# B5_EM__Y_SOLAR_PANEL.net
KiCad netlist of a schematic drawn in EAGLE
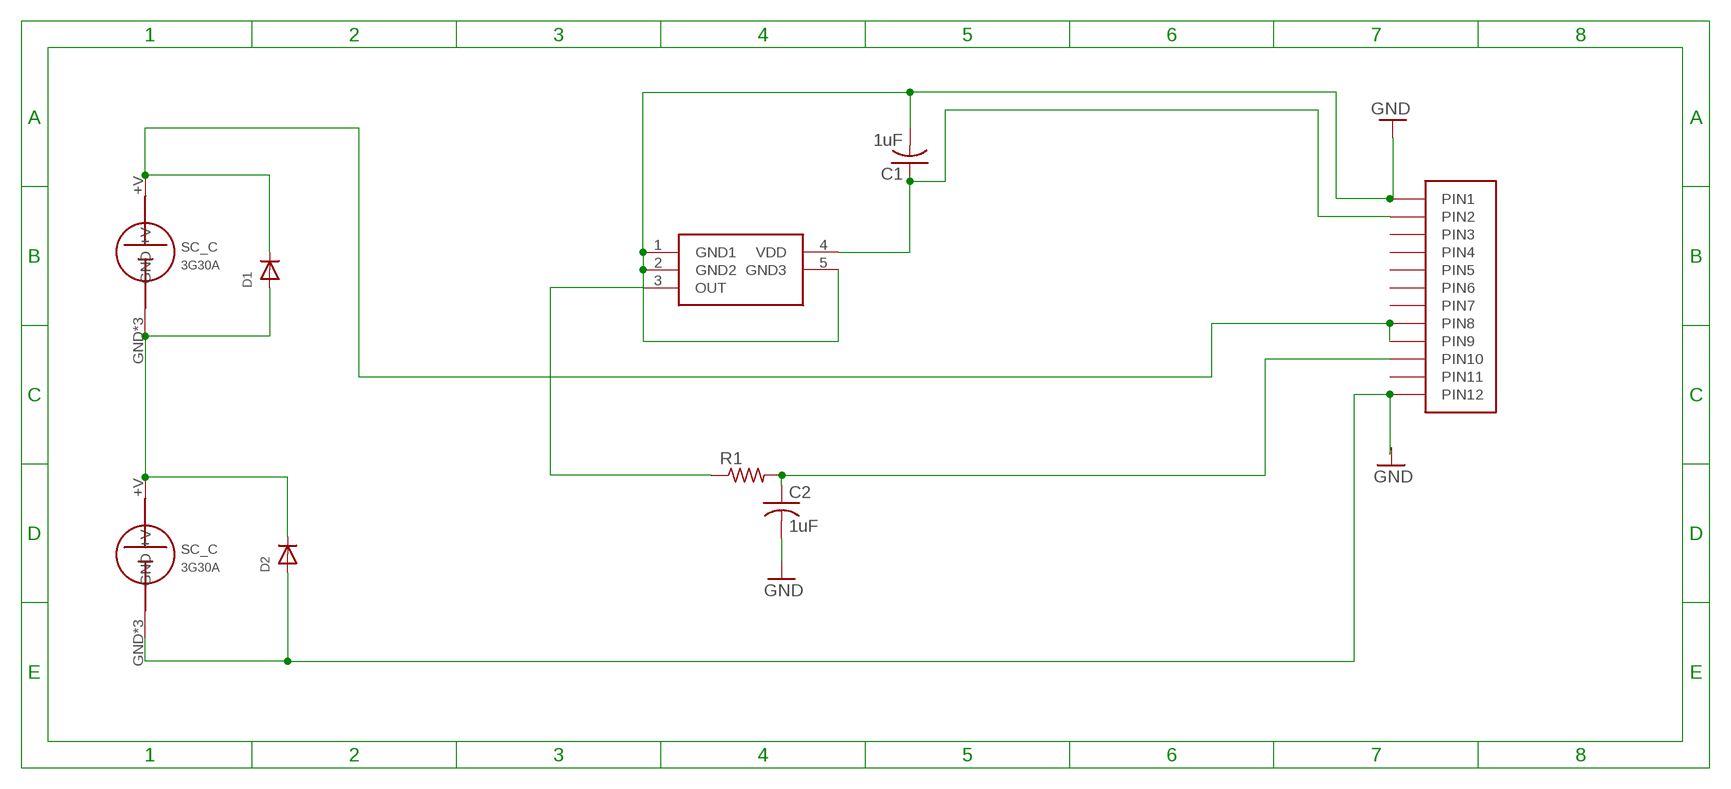
[diagram p0: schematic, sheet 1]

(export (version "E")
  (design (tool "Eeschema 10.0.6"))
  (components
    (comp (ref "C1")
      (value "1uF")
      (footprint "eagle-import:C0805")
      (libsource (lib "eagle-import") (part "C-USC0805"))
    )
    (comp (ref "C2")
      (value "1uF")
      (footprint "eagle-import:C0805")
      (libsource (lib "eagle-import") (part "C-USC0805"))
    )
    (comp (ref "D1")
      (value "DIODE_SOD-123FL")
      (footprint "eagle-import:SOD-123FL")
      (libsource (lib "eagle-import") (part "DIODE_SOD-123FL"))
    )
    (comp (ref "D2")
      (value "DIODE_SOD-123FL")
      (footprint "eagle-import:SOD-123FL")
      (libsource (lib "eagle-import") (part "DIODE_SOD-123FL"))
    )
    (comp (ref "R1")
      (value "R-US_R0402")
      (footprint "eagle-import:R0402")
      (libsource (lib "eagle-import") (part "R-US_R0402"))
    )
    (comp (ref "U$1")
      (value "HEADER12PIN")
      (footprint "eagle-import:HEADER12PIN")
      (libsource (lib "eagle-import") (part "HEADER12PIN"))
    )
    (comp (ref "U$3")
      (value "LMT84DCKT")
      (footprint "eagle-import:SOT65P210X110-5N")
      (fields (field (name "RS_PART_NUMBER") "8115860"))
      (libsource (lib "eagle-import") (part "LMT84DCKT"))
    )
    (comp (ref "U$4")
      (value "SC_C")
      (footprint "eagle-import:SC_C")
      (libsource (lib "eagle-import") (part "SC_C"))
    )
    (comp (ref "U$5")
      (value "SC_C")
      (footprint "eagle-import:SC_C")
      (libsource (lib "eagle-import") (part "SC_C"))
    )
  )
  (nets
    (net (code "1") (name "GND") (class "Default")
      (node (ref "C1") (pin "2") (pinfunction "2_2") (pintype "passive"))
      (node (ref "C2") (pin "2") (pinfunction "2_2") (pintype "passive"))
      (node (ref "D2") (pin "A") (pinfunction "A_A") (pintype "passive"))
      (node (ref "U$1") (pin "P1") (pinfunction "PIN1_P1") (pintype "bidirectional"))
      (node (ref "U$1") (pin "P12") (pinfunction "PIN12_P12") (pintype "bidirectional"))
      (node (ref "U$3") (pin "1") (pinfunction "GND1_1") (pintype "power_in"))
      (node (ref "U$3") (pin "2") (pinfunction "GND2_2") (pintype "power_in"))
      (node (ref "U$3") (pin "5") (pinfunction "GND3_5") (pintype "power_in"))
      (node (ref "U$4") (pin "GND") (pinfunction "GND_GND") (pintype "bidirectional"))
      (node (ref "U$4") (pin "GND1") (pinfunction "GND_GND1") (pintype "bidirectional"))
      (node (ref "U$4") (pin "GND2") (pinfunction "GND_GND2") (pintype "bidirectional"))
    )
    (net (code "2") (name "Net-(D1-PadA)") (class "Default")
      (node (ref "D1") (pin "A") (pinfunction "A_A") (pintype "passive"))
      (node (ref "D2") (pin "C") (pinfunction "C_C") (pintype "passive"))
      (node (ref "U$4") (pin "+V") (pinfunction "+V_+V") (pintype "bidirectional"))
      (node (ref "U$5") (pin "GND") (pinfunction "GND_GND") (pintype "bidirectional"))
      (node (ref "U$5") (pin "GND1") (pinfunction "GND_GND1") (pintype "bidirectional"))
      (node (ref "U$5") (pin "GND2") (pinfunction "GND_GND2") (pintype "bidirectional"))
    )
    (net (code "3") (name "Net-(U$1-PIN2)") (class "Default")
      (node (ref "C1") (pin "1") (pinfunction "1_1") (pintype "passive"))
      (node (ref "U$1") (pin "P2") (pinfunction "PIN2_P2") (pintype "bidirectional"))
      (node (ref "U$3") (pin "4") (pinfunction "VDD_4") (pintype "power_in"))
    )
    (net (code "4") (name "Net-(U$1-PIN8)") (class "Default")
      (node (ref "D1") (pin "C") (pinfunction "C_C") (pintype "passive"))
      (node (ref "U$1") (pin "P8") (pinfunction "PIN8_P8") (pintype "bidirectional"))
      (node (ref "U$1") (pin "P9") (pinfunction "PIN9_P9") (pintype "bidirectional"))
      (node (ref "U$5") (pin "+V") (pinfunction "+V_+V") (pintype "bidirectional"))
    )
    (net (code "5") (name "Net-(U$1-PIN10)") (class "Default")
      (node (ref "C2") (pin "1") (pinfunction "1_1") (pintype "passive"))
      (node (ref "R1") (pin "2") (pinfunction "2_2") (pintype "passive"))
      (node (ref "U$1") (pin "P10") (pinfunction "PIN10_P10") (pintype "bidirectional"))
    )
    (net (code "6") (name "Net-(U$3-OUT)") (class "Default")
      (node (ref "R1") (pin "1") (pinfunction "1_1") (pintype "passive"))
      (node (ref "U$3") (pin "3") (pinfunction "OUT_3") (pintype "output"))
    )
    (net (code "7") (name "unconnected-(U$1-PIN3-PadP3)") (class "Default")
      (node (ref "U$1") (pin "P3") (pinfunction "PIN3_P3") (pintype "bidirectional"))
    )
    (net (code "8") (name "unconnected-(U$1-PIN4-PadP4)") (class "Default")
      (node (ref "U$1") (pin "P4") (pinfunction "PIN4_P4") (pintype "bidirectional"))
    )
    (net (code "9") (name "unconnected-(U$1-PIN5-PadP5)") (class "Default")
      (node (ref "U$1") (pin "P5") (pinfunction "PIN5_P5") (pintype "bidirectional"))
    )
    (net (code "10") (name "unconnected-(U$1-PIN6-PadP6)") (class "Default")
      (node (ref "U$1") (pin "P6") (pinfunction "PIN6_P6") (pintype "bidirectional"))
    )
    (net (code "11") (name "unconnected-(U$1-PIN7-PadP7)") (class "Default")
      (node (ref "U$1") (pin "P7") (pinfunction "PIN7_P7") (pintype "bidirectional"))
    )
    (net (code "12") (name "unconnected-(U$1-PIN11-PadP11)") (class "Default")
      (node (ref "U$1") (pin "P11") (pinfunction "PIN11_P11") (pintype "bidirectional"))
    )
  )
)
